# SC_customized2.net
KiCad netlist of a schematic drawn in EAGLE
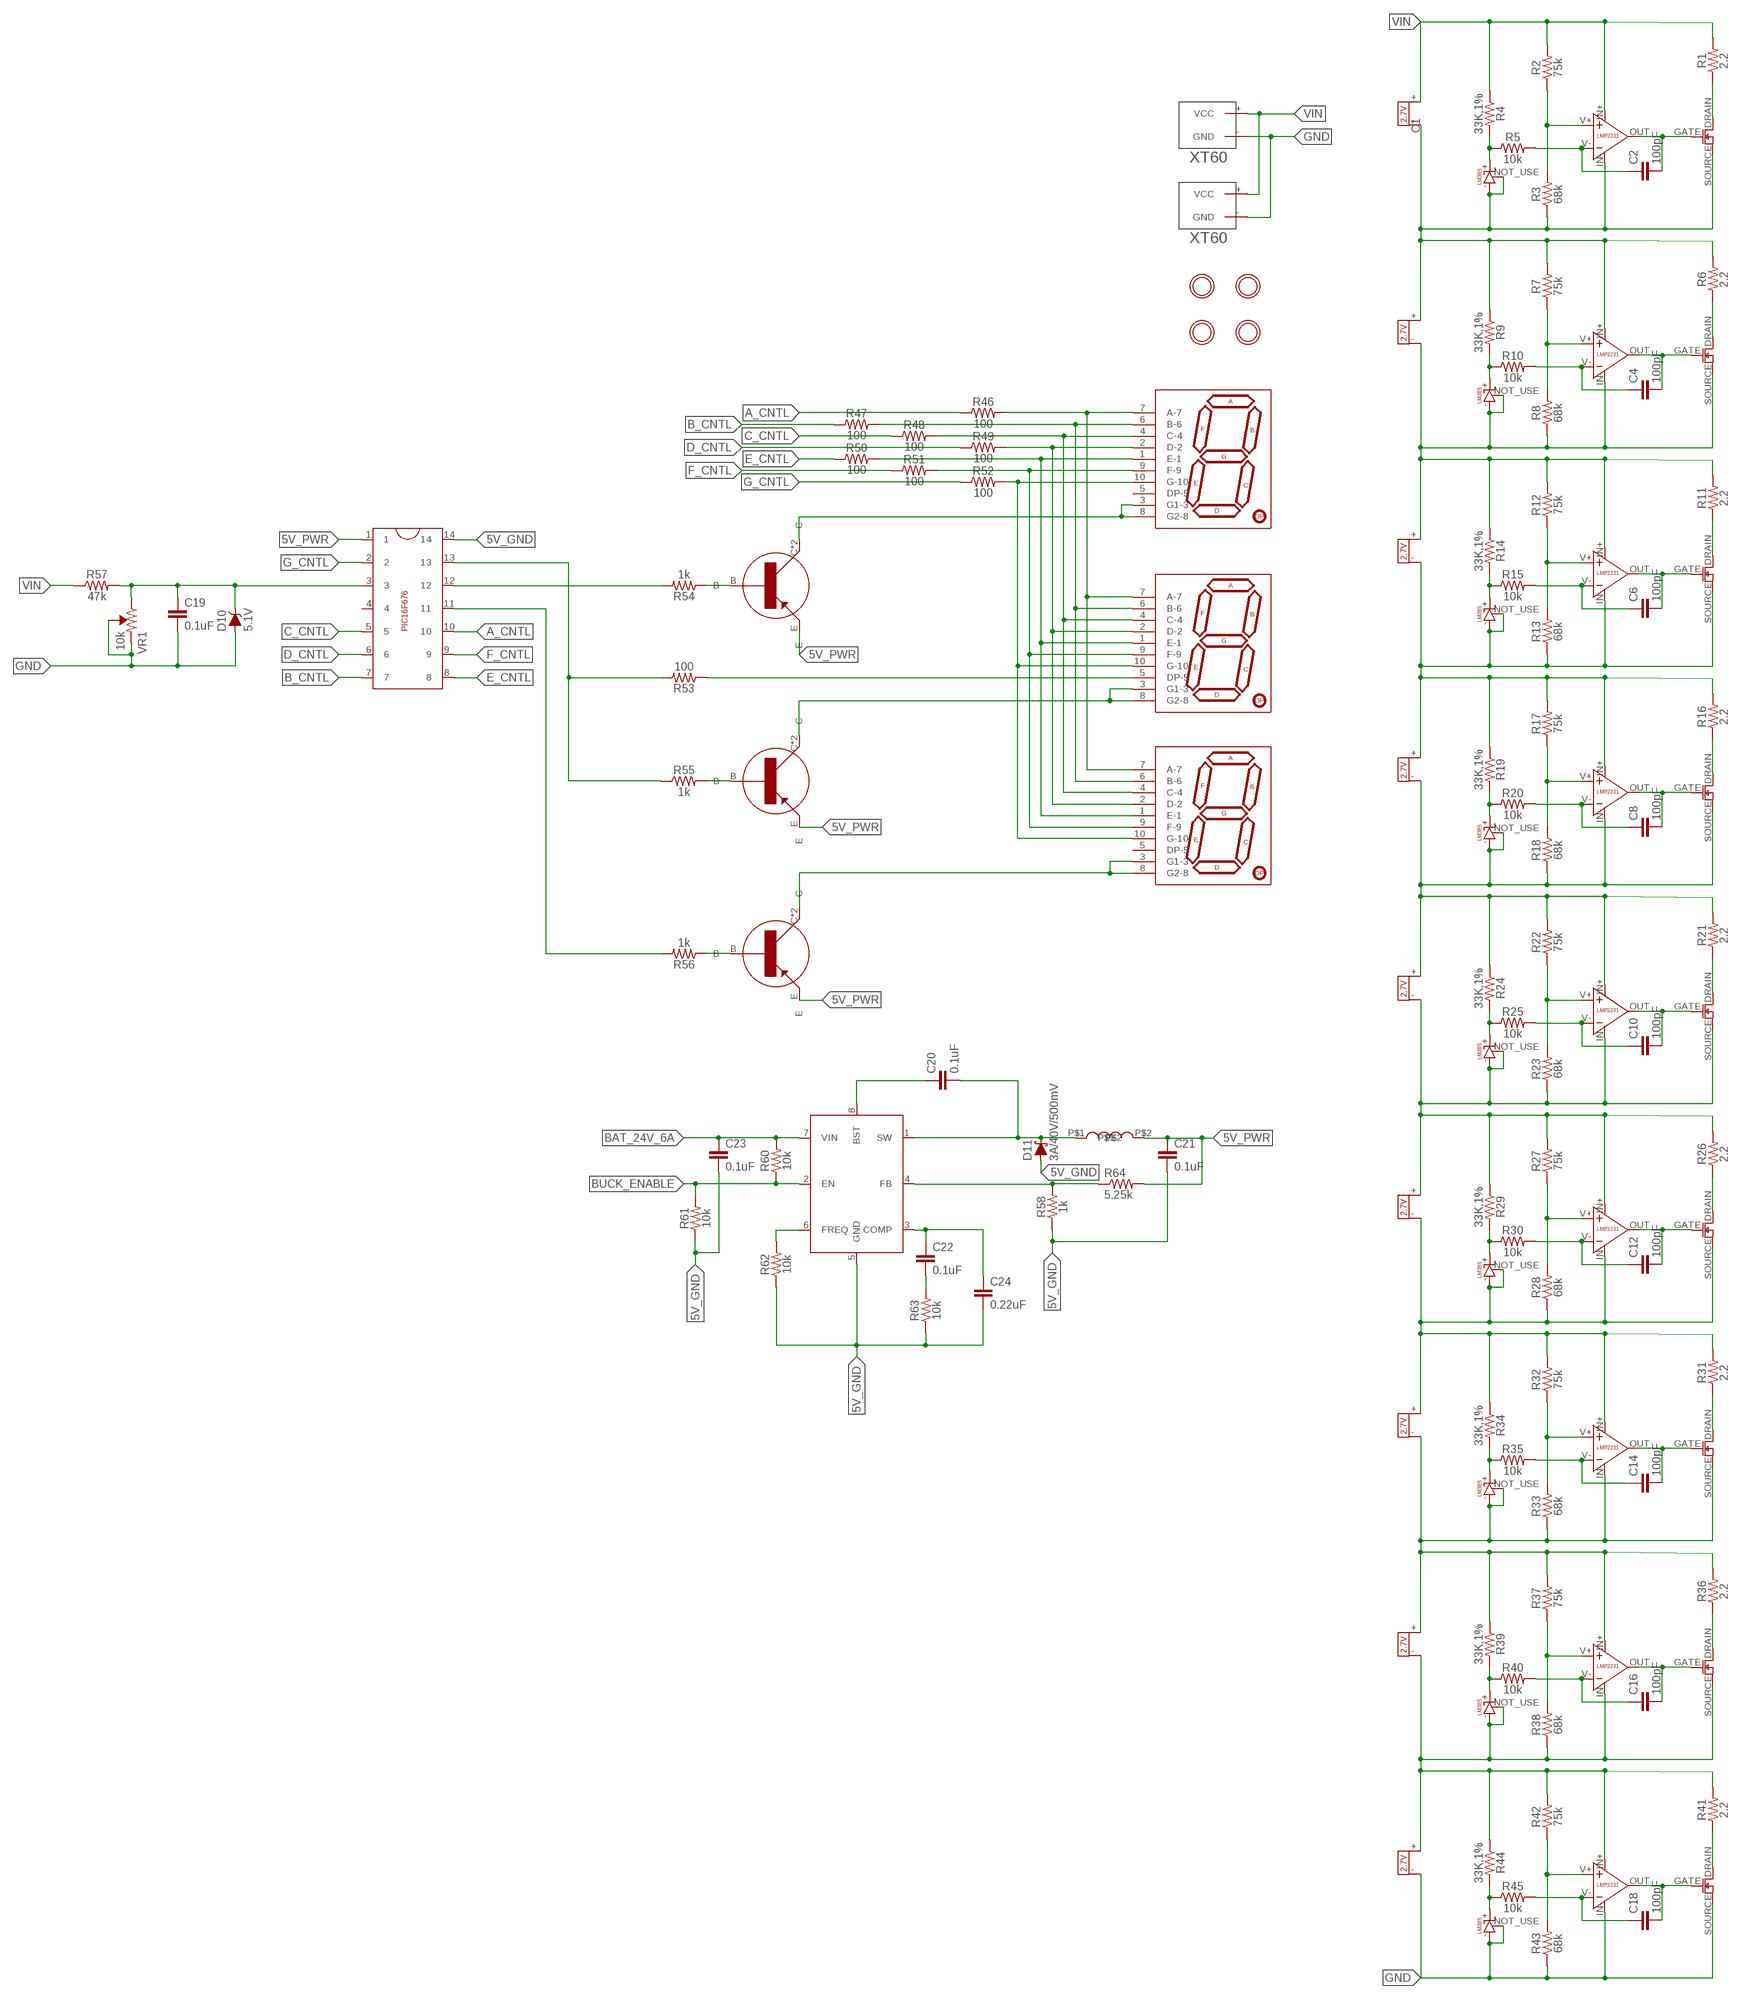
[diagram p0: schematic, sheet 1]

(export (version "E")
  (design (tool "Eeschema 10.0.6"))
  (components
    (comp (ref "3.3V_BUCK")
      (value "SOIC8E")
      (footprint "eagle-import:SOIC127P600X170-9N")
      (libsource (lib "eagle-import") (part "SOIC8E"))
    )
    (comp (ref "C1")
      (value "2.7V 60F")
      (footprint "eagle-import:2.7V_60F")
      (libsource (lib "eagle-import") (part "2.7V_60F"))
    )
    (comp (ref "C2")
      (value "100pF")
      (footprint "eagle-import:0603")
      (libsource (lib "eagle-import") (part "100PF-0603-50V-5%"))
    )
    (comp (ref "C3")
      (value "2.7V 60F")
      (footprint "eagle-import:2.7V_60F")
      (libsource (lib "eagle-import") (part "2.7V_60F"))
    )
    (comp (ref "C4")
      (value "100pF")
      (footprint "eagle-import:0603")
      (libsource (lib "eagle-import") (part "100PF-0603-50V-5%"))
    )
    (comp (ref "C5")
      (value "2.7V 60F")
      (footprint "eagle-import:2.7V_60F")
      (libsource (lib "eagle-import") (part "2.7V_60F"))
    )
    (comp (ref "C6")
      (value "100pF")
      (footprint "eagle-import:0603")
      (libsource (lib "eagle-import") (part "100PF-0603-50V-5%"))
    )
    (comp (ref "C7")
      (value "2.7V 60F")
      (footprint "eagle-import:2.7V_60F")
      (libsource (lib "eagle-import") (part "2.7V_60F"))
    )
    (comp (ref "C8")
      (value "100pF")
      (footprint "eagle-import:0603")
      (libsource (lib "eagle-import") (part "100PF-0603-50V-5%"))
    )
    (comp (ref "C9")
      (value "2.7V 60F")
      (footprint "eagle-import:2.7V_60F")
      (libsource (lib "eagle-import") (part "2.7V_60F"))
    )
    (comp (ref "C10")
      (value "100pF")
      (footprint "eagle-import:0603")
      (libsource (lib "eagle-import") (part "100PF-0603-50V-5%"))
    )
    (comp (ref "C11")
      (value "2.7V 60F")
      (footprint "eagle-import:2.7V_60F")
      (libsource (lib "eagle-import") (part "2.7V_60F"))
    )
    (comp (ref "C12")
      (value "100pF")
      (footprint "eagle-import:0603")
      (libsource (lib "eagle-import") (part "100PF-0603-50V-5%"))
    )
    (comp (ref "C13")
      (value "2.7V 60F")
      (footprint "eagle-import:2.7V_60F")
      (libsource (lib "eagle-import") (part "2.7V_60F"))
    )
    (comp (ref "C14")
      (value "100pF")
      (footprint "eagle-import:0603")
      (libsource (lib "eagle-import") (part "100PF-0603-50V-5%"))
    )
    (comp (ref "C15")
      (value "2.7V 60F")
      (footprint "eagle-import:2.7V_60F")
      (libsource (lib "eagle-import") (part "2.7V_60F"))
    )
    (comp (ref "C16")
      (value "100pF")
      (footprint "eagle-import:0603")
      (libsource (lib "eagle-import") (part "100PF-0603-50V-5%"))
    )
    (comp (ref "C17")
      (value "2.7V 60F")
      (footprint "eagle-import:2.7V_60F")
      (libsource (lib "eagle-import") (part "2.7V_60F"))
    )
    (comp (ref "C18")
      (value "100pF")
      (footprint "eagle-import:0603")
      (libsource (lib "eagle-import") (part "100PF-0603-50V-5%"))
    )
    (comp (ref "C19")
      (value "0.1uF")
      (footprint "eagle-import:0603")
      (libsource (lib "eagle-import") (part "SparkFun-Capacitors_510_0.1UF-0603-25V-5%"))
    )
    (comp (ref "C20")
      (value "0.1uF")
      (footprint "eagle-import:0603")
      (libsource (lib "eagle-import") (part "0.1UF-0603-25V-(+80/-20%)"))
    )
    (comp (ref "C21")
      (value "0.1uF")
      (footprint "eagle-import:0603")
      (libsource (lib "eagle-import") (part "0.1UF-0603-25V-(+80/-20%)"))
    )
    (comp (ref "C22")
      (value "0.1uF")
      (footprint "eagle-import:0603")
      (libsource (lib "eagle-import") (part "0.1UF-0603-25V-(+80/-20%)"))
    )
    (comp (ref "C23")
      (value "0.1uF")
      (footprint "eagle-import:0603")
      (libsource (lib "eagle-import") (part "0.1UF-0603-25V-(+80/-20%)"))
    )
    (comp (ref "C24")
      (value "0.22uF")
      (footprint "eagle-import:0603")
      (libsource (lib "eagle-import") (part "0.22UF-0603-50V-(-20/+80%)"))
    )
    (comp (ref "D1")
      (value "LM385")
      (footprint "eagle-import:LM385_SOT23")
      (libsource (lib "eagle-import") (part "LM385"))
    )
    (comp (ref "D2")
      (value "LM385")
      (footprint "eagle-import:LM385_SOT23")
      (libsource (lib "eagle-import") (part "LM385"))
    )
    (comp (ref "D3")
      (value "LM385")
      (footprint "eagle-import:LM385_SOT23")
      (libsource (lib "eagle-import") (part "LM385"))
    )
    (comp (ref "D4")
      (value "LM385")
      (footprint "eagle-import:LM385_SOT23")
      (libsource (lib "eagle-import") (part "LM385"))
    )
    (comp (ref "D5")
      (value "LM385")
      (footprint "eagle-import:LM385_SOT23")
      (libsource (lib "eagle-import") (part "LM385"))
    )
    (comp (ref "D6")
      (value "LM385")
      (footprint "eagle-import:LM385_SOT23")
      (libsource (lib "eagle-import") (part "LM385"))
    )
    (comp (ref "D7")
      (value "LM385")
      (footprint "eagle-import:LM385_SOT23")
      (libsource (lib "eagle-import") (part "LM385"))
    )
    (comp (ref "D8")
      (value "LM385")
      (footprint "eagle-import:LM385_SOT23")
      (libsource (lib "eagle-import") (part "LM385"))
    )
    (comp (ref "D9")
      (value "LM385")
      (footprint "eagle-import:LM385_SOT23")
      (libsource (lib "eagle-import") (part "LM385"))
    )
    (comp (ref "D10")
      (value "5.1V")
      (footprint "eagle-import:SOD-323")
      (libsource (lib "eagle-import") (part "DIODE-ZENER-MMSZ5232BS"))
    )
    (comp (ref "D11")
      (value "3A/40V/500mV")
      (footprint "eagle-import:SMA-DIODE")
      (libsource (lib "eagle-import") (part "DIODE-SCHOTTKY-B340A"))
    )
    (comp (ref "LMP1")
      (value "LMP2231")
      (footprint "eagle-import:LMP2231_SOT23_5")
      (libsource (lib "eagle-import") (part "LMP2231"))
    )
    (comp (ref "LMP2")
      (value "LMP2231")
      (footprint "eagle-import:LMP2231_SOT23_5")
      (libsource (lib "eagle-import") (part "LMP2231"))
    )
    (comp (ref "LMP3")
      (value "LMP2231")
      (footprint "eagle-import:LMP2231_SOT23_5")
      (libsource (lib "eagle-import") (part "LMP2231"))
    )
    (comp (ref "LMP4")
      (value "LMP2231")
      (footprint "eagle-import:LMP2231_SOT23_5")
      (libsource (lib "eagle-import") (part "LMP2231"))
    )
    (comp (ref "LMP5")
      (value "LMP2231")
      (footprint "eagle-import:LMP2231_SOT23_5")
      (libsource (lib "eagle-import") (part "LMP2231"))
    )
    (comp (ref "LMP6")
      (value "LMP2231")
      (footprint "eagle-import:LMP2231_SOT23_5")
      (libsource (lib "eagle-import") (part "LMP2231"))
    )
    (comp (ref "LMP7")
      (value "LMP2231")
      (footprint "eagle-import:LMP2231_SOT23_5")
      (libsource (lib "eagle-import") (part "LMP2231"))
    )
    (comp (ref "LMP8")
      (value "LMP2231")
      (footprint "eagle-import:LMP2231_SOT23_5")
      (libsource (lib "eagle-import") (part "LMP2231"))
    )
    (comp (ref "LMP9")
      (value "LMP2231")
      (footprint "eagle-import:LMP2231_SOT23_5")
      (libsource (lib "eagle-import") (part "LMP2231"))
    )
    (comp (ref "MOS1")
      (value "IRLML2502TRPBF_MOS")
      (footprint "eagle-import:IRLML2502TRPBF_SOT23")
      (libsource (lib "eagle-import") (part "IRLML2502TRPBF_MOS"))
    )
    (comp (ref "MOS2")
      (value "IRLML2502TRPBF_MOS")
      (footprint "eagle-import:IRLML2502TRPBF_SOT23")
      (libsource (lib "eagle-import") (part "IRLML2502TRPBF_MOS"))
    )
    (comp (ref "MOS3")
      (value "IRLML2502TRPBF_MOS")
      (footprint "eagle-import:IRLML2502TRPBF_SOT23")
      (libsource (lib "eagle-import") (part "IRLML2502TRPBF_MOS"))
    )
    (comp (ref "MOS4")
      (value "IRLML2502TRPBF_MOS")
      (footprint "eagle-import:IRLML2502TRPBF_SOT23")
      (libsource (lib "eagle-import") (part "IRLML2502TRPBF_MOS"))
    )
    (comp (ref "MOS5")
      (value "IRLML2502TRPBF_MOS")
      (footprint "eagle-import:IRLML2502TRPBF_SOT23")
      (libsource (lib "eagle-import") (part "IRLML2502TRPBF_MOS"))
    )
    (comp (ref "MOS6")
      (value "IRLML2502TRPBF_MOS")
      (footprint "eagle-import:IRLML2502TRPBF_SOT23")
      (libsource (lib "eagle-import") (part "IRLML2502TRPBF_MOS"))
    )
    (comp (ref "MOS7")
      (value "IRLML2502TRPBF_MOS")
      (footprint "eagle-import:IRLML2502TRPBF_SOT23")
      (libsource (lib "eagle-import") (part "IRLML2502TRPBF_MOS"))
    )
    (comp (ref "MOS8")
      (value "IRLML2502TRPBF_MOS")
      (footprint "eagle-import:IRLML2502TRPBF_SOT23")
      (libsource (lib "eagle-import") (part "IRLML2502TRPBF_MOS"))
    )
    (comp (ref "MOS9")
      (value "IRLML2502TRPBF_MOS")
      (footprint "eagle-import:IRLML2502TRPBF_SOT23")
      (libsource (lib "eagle-import") (part "IRLML2502TRPBF_MOS"))
    )
    (comp (ref "PWR_IN")
      (value "XT60")
      (footprint "eagle-import:XT60")
      (libsource (lib "eagle-import") (part "XT60"))
    )
    (comp (ref "PWR_OUT")
      (value "XT60")
      (footprint "eagle-import:XT60")
      (libsource (lib "eagle-import") (part "XT60"))
    )
    (comp (ref "R1")
      (value "2.2")
      (footprint "eagle-import:2512")
      (libsource (lib "eagle-import") (part "0.05OHM-2512-3W-1%"))
    )
    (comp (ref "R2")
      (value "75k")
      (footprint "eagle-import:0603@1")
      (libsource (lib "eagle-import") (part "75KOHM-0603-1/10W-1%"))
    )
    (comp (ref "R3")
      (value "68k")
      (footprint "eagle-import:0603@1")
      (libsource (lib "eagle-import") (part "75KOHM-0603-1/10W-1%"))
    )
    (comp (ref "R4")
      (value "33K,1%")
      (footprint "eagle-import:0603@1")
      (libsource (lib "eagle-import") (part "1MOHM-0603-1/4W-5%"))
    )
    (comp (ref "R5")
      (value "10k")
      (footprint "eagle-import:0603")
      (libsource (lib "eagle-import") (part "10KOHM-0603-1/10W-1%"))
    )
    (comp (ref "R6")
      (value "2.2")
      (footprint "eagle-import:2512")
      (libsource (lib "eagle-import") (part "0.05OHM-2512-3W-1%"))
    )
    (comp (ref "R7")
      (value "75k")
      (footprint "eagle-import:0603@1")
      (libsource (lib "eagle-import") (part "75KOHM-0603-1/10W-1%"))
    )
    (comp (ref "R8")
      (value "68k")
      (footprint "eagle-import:0603@1")
      (libsource (lib "eagle-import") (part "75KOHM-0603-1/10W-1%"))
    )
    (comp (ref "R9")
      (value "33K,1%")
      (footprint "eagle-import:0603@1")
      (libsource (lib "eagle-import") (part "1MOHM-0603-1/4W-5%"))
    )
    (comp (ref "R10")
      (value "10k")
      (footprint "eagle-import:0603")
      (libsource (lib "eagle-import") (part "10KOHM-0603-1/10W-1%"))
    )
    (comp (ref "R11")
      (value "2.2")
      (footprint "eagle-import:2512")
      (libsource (lib "eagle-import") (part "0.05OHM-2512-3W-1%"))
    )
    (comp (ref "R12")
      (value "75k")
      (footprint "eagle-import:0603@1")
      (libsource (lib "eagle-import") (part "75KOHM-0603-1/10W-1%"))
    )
    (comp (ref "R13")
      (value "68k")
      (footprint "eagle-import:0603@1")
      (libsource (lib "eagle-import") (part "75KOHM-0603-1/10W-1%"))
    )
    (comp (ref "R14")
      (value "33K,1%")
      (footprint "eagle-import:0603@1")
      (libsource (lib "eagle-import") (part "1MOHM-0603-1/4W-5%"))
    )
    (comp (ref "R15")
      (value "10k")
      (footprint "eagle-import:0603")
      (libsource (lib "eagle-import") (part "10KOHM-0603-1/10W-1%"))
    )
    (comp (ref "R16")
      (value "2.2")
      (footprint "eagle-import:2512")
      (libsource (lib "eagle-import") (part "0.05OHM-2512-3W-1%"))
    )
    (comp (ref "R17")
      (value "75k")
      (footprint "eagle-import:0603@1")
      (libsource (lib "eagle-import") (part "75KOHM-0603-1/10W-1%"))
    )
    (comp (ref "R18")
      (value "68k")
      (footprint "eagle-import:0603@1")
      (libsource (lib "eagle-import") (part "75KOHM-0603-1/10W-1%"))
    )
    (comp (ref "R19")
      (value "33K,1%")
      (footprint "eagle-import:0603@1")
      (libsource (lib "eagle-import") (part "1MOHM-0603-1/4W-5%"))
    )
    (comp (ref "R20")
      (value "10k")
      (footprint "eagle-import:0603")
      (libsource (lib "eagle-import") (part "10KOHM-0603-1/10W-1%"))
    )
    (comp (ref "R21")
      (value "2.2")
      (footprint "eagle-import:2512")
      (libsource (lib "eagle-import") (part "0.05OHM-2512-3W-1%"))
    )
    (comp (ref "R22")
      (value "75k")
      (footprint "eagle-import:0603@1")
      (libsource (lib "eagle-import") (part "75KOHM-0603-1/10W-1%"))
    )
    (comp (ref "R23")
      (value "68k")
      (footprint "eagle-import:0603@1")
      (libsource (lib "eagle-import") (part "75KOHM-0603-1/10W-1%"))
    )
    (comp (ref "R24")
      (value "33K,1%")
      (footprint "eagle-import:0603@1")
      (libsource (lib "eagle-import") (part "1MOHM-0603-1/4W-5%"))
    )
    (comp (ref "R25")
      (value "10k")
      (footprint "eagle-import:0603")
      (libsource (lib "eagle-import") (part "10KOHM-0603-1/10W-1%"))
    )
    (comp (ref "R26")
      (value "2.2")
      (footprint "eagle-import:2512")
      (libsource (lib "eagle-import") (part "0.05OHM-2512-3W-1%"))
    )
    (comp (ref "R27")
      (value "75k")
      (footprint "eagle-import:0603@1")
      (libsource (lib "eagle-import") (part "75KOHM-0603-1/10W-1%"))
    )
    (comp (ref "R28")
      (value "68k")
      (footprint "eagle-import:0603@1")
      (libsource (lib "eagle-import") (part "75KOHM-0603-1/10W-1%"))
    )
    (comp (ref "R29")
      (value "33K,1%")
      (footprint "eagle-import:0603@1")
      (libsource (lib "eagle-import") (part "1MOHM-0603-1/4W-5%"))
    )
    (comp (ref "R30")
      (value "10k")
      (footprint "eagle-import:0603")
      (libsource (lib "eagle-import") (part "10KOHM-0603-1/10W-1%"))
    )
    (comp (ref "R31")
      (value "2.2")
      (footprint "eagle-import:2512")
      (libsource (lib "eagle-import") (part "0.05OHM-2512-3W-1%"))
    )
    (comp (ref "R32")
      (value "75k")
      (footprint "eagle-import:0603@1")
      (libsource (lib "eagle-import") (part "75KOHM-0603-1/10W-1%"))
    )
    (comp (ref "R33")
      (value "68k")
      (footprint "eagle-import:0603@1")
      (libsource (lib "eagle-import") (part "75KOHM-0603-1/10W-1%"))
    )
    (comp (ref "R34")
      (value "33K,1%")
      (footprint "eagle-import:0603@1")
      (libsource (lib "eagle-import") (part "1MOHM-0603-1/4W-5%"))
    )
    (comp (ref "R35")
      (value "10k")
      (footprint "eagle-import:0603")
      (libsource (lib "eagle-import") (part "10KOHM-0603-1/10W-1%"))
    )
    (comp (ref "R36")
      (value "2.2")
      (footprint "eagle-import:2512")
      (libsource (lib "eagle-import") (part "0.05OHM-2512-3W-1%"))
    )
    (comp (ref "R37")
      (value "75k")
      (footprint "eagle-import:0603@1")
      (libsource (lib "eagle-import") (part "75KOHM-0603-1/10W-1%"))
    )
    (comp (ref "R38")
      (value "68k")
      (footprint "eagle-import:0603@1")
      (libsource (lib "eagle-import") (part "75KOHM-0603-1/10W-1%"))
    )
    (comp (ref "R39")
      (value "33K,1%")
      (footprint "eagle-import:0603@1")
      (libsource (lib "eagle-import") (part "1MOHM-0603-1/4W-5%"))
    )
    (comp (ref "R40")
      (value "10k")
      (footprint "eagle-import:0603")
      (libsource (lib "eagle-import") (part "10KOHM-0603-1/10W-1%"))
    )
    (comp (ref "R41")
      (value "2.2")
      (footprint "eagle-import:2512")
      (libsource (lib "eagle-import") (part "0.05OHM-2512-3W-1%"))
    )
    (comp (ref "R42")
      (value "75k")
      (footprint "eagle-import:0603@1")
      (libsource (lib "eagle-import") (part "75KOHM-0603-1/10W-1%"))
    )
    (comp (ref "R43")
      (value "68k")
      (footprint "eagle-import:0603@1")
      (libsource (lib "eagle-import") (part "75KOHM-0603-1/10W-1%"))
    )
    (comp (ref "R44")
      (value "33K,1%")
      (footprint "eagle-import:0603@1")
      (libsource (lib "eagle-import") (part "1MOHM-0603-1/4W-5%"))
    )
    (comp (ref "R45")
      (value "10k")
      (footprint "eagle-import:0603")
      (libsource (lib "eagle-import") (part "10KOHM-0603-1/10W-1%"))
    )
    (comp (ref "R46")
      (value "100")
      (footprint "eagle-import:0603")
      (libsource (lib "eagle-import") (part "100OHM-0603-1/4W-5%"))
    )
    (comp (ref "R47")
      (value "100")
      (footprint "eagle-import:0603")
      (libsource (lib "eagle-import") (part "100OHM-0603-1/4W-5%"))
    )
    (comp (ref "R48")
      (value "100")
      (footprint "eagle-import:0603")
      (libsource (lib "eagle-import") (part "100OHM-0603-1/4W-5%"))
    )
    (comp (ref "R49")
      (value "100")
      (footprint "eagle-import:0603")
      (libsource (lib "eagle-import") (part "100OHM-0603-1/4W-5%"))
    )
    (comp (ref "R50")
      (value "100")
      (footprint "eagle-import:0603")
      (libsource (lib "eagle-import") (part "100OHM-0603-1/4W-5%"))
    )
    (comp (ref "R51")
      (value "100")
      (footprint "eagle-import:0603")
      (libsource (lib "eagle-import") (part "100OHM-0603-1/4W-5%"))
    )
    (comp (ref "R52")
      (value "100")
      (footprint "eagle-import:0603")
      (libsource (lib "eagle-import") (part "100OHM-0603-1/4W-5%"))
    )
    (comp (ref "R53")
      (value "100")
      (footprint "eagle-import:0603")
      (libsource (lib "eagle-import") (part "100OHM-0603-1/4W-5%"))
    )
    (comp (ref "R54")
      (value "1k")
      (footprint "eagle-import:0603")
      (libsource (lib "eagle-import") (part "SparkFun-Resistors_532_1KOHM-0603-1/10W-1%"))
    )
    (comp (ref "R55")
      (value "1k")
      (footprint "eagle-import:0603")
      (libsource (lib "eagle-import") (part "SparkFun-Resistors_532_1KOHM-0603-1/10W-1%"))
    )
    (comp (ref "R56")
      (value "1k")
      (footprint "eagle-import:0603")
      (libsource (lib "eagle-import") (part "SparkFun-Resistors_532_1KOHM-0603-1/10W-1%"))
    )
    (comp (ref "R57")
      (value "47k")
      (footprint "eagle-import:0603")
      (libsource (lib "eagle-import") (part "47KOHM-0603-1/10W-1%"))
    )
    (comp (ref "R58")
      (value "1k")
      (footprint "eagle-import:0603")
      (libsource (lib "eagle-import") (part "1KOHM-0603-1/10W-1%"))
    )
    (comp (ref "R60")
      (value "10k")
      (footprint "eagle-import:0603")
      (libsource (lib "eagle-import") (part "10KOHM-0603-1/10W-1%"))
    )
    (comp (ref "R61")
      (value "10k")
      (footprint "eagle-import:0603")
      (libsource (lib "eagle-import") (part "10KOHM-0603-1/10W-1%"))
    )
    (comp (ref "R62")
      (value "10k")
      (footprint "eagle-import:0603")
      (libsource (lib "eagle-import") (part "10KOHM-0603-1/10W-1%"))
    )
    (comp (ref "R63")
      (value "10k")
      (footprint "eagle-import:0603")
      (libsource (lib "eagle-import") (part "10KOHM-0603-1/10W-1%"))
    )
    (comp (ref "R64")
      (value "5.25k")
      (footprint "eagle-import:RES_0805")
      (fields
        (field (name "DIGIKEY_PART_NUMBER") "541-0.0ATR-ND")
        (field (name "MANUFACTURER") "Vishay Dale")
        (field (name "MPN") "CRCW08050000Z0EA")
        (field (name "CREATED_BY") "PCBLayout.com")
      )
      (libsource (lib "eagle-import") (part "CRCW08050000Z0EA"))
    )
    (comp (ref "U$1")
      (value "MOUNTINGHOLE2.5")
      (footprint "eagle-import:MOUNTINGHOLE_2.5_PLATED")
      (libsource (lib "eagle-import") (part "MOUNTINGHOLE2.5"))
    )
    (comp (ref "U$2")
      (value "MOUNTINGHOLE2.5")
      (footprint "eagle-import:MOUNTINGHOLE_2.5_PLATED")
      (libsource (lib "eagle-import") (part "MOUNTINGHOLE2.5"))
    )
    (comp (ref "U$3")
      (value "PZT3906")
      (footprint "eagle-import:SOT_223")
      (libsource (lib "eagle-import") (part "PZT3906"))
    )
    (comp (ref "U$4")
      (value "MOUNTINGHOLE2.5")
      (footprint "eagle-import:MOUNTINGHOLE_2.5_PLATED")
      (libsource (lib "eagle-import") (part "MOUNTINGHOLE2.5"))
    )
    (comp (ref "U$5")
      (value "PZT3906")
      (footprint "eagle-import:SOT_223")
      (libsource (lib "eagle-import") (part "PZT3906"))
    )
    (comp (ref "U$6")
      (value "PZT3906")
      (footprint "eagle-import:SOT_223")
      (libsource (lib "eagle-import") (part "PZT3906"))
    )
    (comp (ref "U$7")
      (value "DSM7T")
      (footprint "eagle-import:7-SEGMENT_SMD")
      (libsource (lib "eagle-import") (part "DSM7T"))
    )
    (comp (ref "U$8")
      (value "DSM7T")
      (footprint "eagle-import:7-SEGMENT_SMD")
      (libsource (lib "eagle-import") (part "DSM7T"))
    )
    (comp (ref "U$9")
      (value "DSM7T")
      (footprint "eagle-import:7-SEGMENT_SMD")
      (libsource (lib "eagle-import") (part "DSM7T"))
    )
    (comp (ref "U$10")
      (value "PIC16F676")
      (footprint "eagle-import:PIC16F676")
      (libsource (lib "eagle-import") (part "PIC16F676"))
    )
    (comp (ref "U$11")
      (value "4.7UH_INDUCTOR")
      (footprint "eagle-import:4.7UH_INDUCTOR")
      (libsource (lib "eagle-import") (part "4.7UH_INDUCTOR"))
    )
    (comp (ref "U$49")
      (value "MOUNTINGHOLE2.5")
      (footprint "eagle-import:MOUNTINGHOLE_2.5_PLATED")
      (libsource (lib "eagle-import") (part "MOUNTINGHOLE2.5"))
    )
    (comp (ref "VR1")
      (value "10k")
      (footprint "eagle-import:TRIMPOT-SMD-TC33X")
      (libsource (lib "eagle-import") (part "TRIMPOT-SMD-3MM-OPEN-1/10W-25%"))
    )
  )
  (nets
    (net (code "1") (name "5V_GND") (class "Default")
      (node (ref "3.3V_BUCK") (pin "5") (pinfunction "GND_5") (pintype "bidirectional"))
      (node (ref "C21") (pin "2") (pinfunction "2_2") (pintype "passive"))
      (node (ref "C23") (pin "2") (pinfunction "2_2") (pintype "passive"))
      (node (ref "C24") (pin "2") (pinfunction "2_2") (pintype "passive"))
      (node (ref "D11") (pin "A") (pinfunction "A_A") (pintype "passive"))
      (node (ref "R58") (pin "1") (pinfunction "1_1") (pintype "passive"))
      (node (ref "R61") (pin "1") (pinfunction "1_1") (pintype "passive"))
      (node (ref "R62") (pin "1") (pinfunction "1_1") (pintype "passive"))
      (node (ref "R63") (pin "1") (pinfunction "1_1") (pintype "passive"))
      (node (ref "U$10") (pin "14") (pinfunction "14_14") (pintype "bidirectional"))
    )
    (net (code "2") (name "5V_PWR") (class "Default")
      (node (ref "C21") (pin "1") (pinfunction "1_1") (pintype "passive"))
      (node (ref "R64") (pin "2") (pinfunction "2_2") (pintype "passive"))
      (node (ref "U$10") (pin "1") (pinfunction "1_1") (pintype "bidirectional"))
      (node (ref "U$11") (pin "P$2") (pinfunction "P$2_P$2") (pintype "bidirectional"))
      (node (ref "U$3") (pin "E") (pinfunction "E_E") (pintype "bidirectional"))
      (node (ref "U$5") (pin "E") (pinfunction "E_E") (pintype "bidirectional"))
      (node (ref "U$6") (pin "E") (pinfunction "E_E") (pintype "bidirectional"))
    )
    (net (code "3") (name "A_CNTL") (class "Default")
      (node (ref "R46") (pin "1") (pinfunction "1_1") (pintype "passive"))
      (node (ref "U$10") (pin "10") (pinfunction "10_10") (pintype "bidirectional"))
    )
    (net (code "4") (name "BAT_24V_6A") (class "Default")
      (node (ref "3.3V_BUCK") (pin "7") (pinfunction "VIN_7") (pintype "bidirectional"))
      (node (ref "C23") (pin "1") (pinfunction "1_1") (pintype "passive"))
      (node (ref "R60") (pin "2") (pinfunction "2_2") (pintype "passive"))
    )
    (net (code "5") (name "BUCK_ENABLE") (class "Default")
      (node (ref "3.3V_BUCK") (pin "2") (pinfunction "EN_2") (pintype "bidirectional"))
      (node (ref "R60") (pin "1") (pinfunction "1_1") (pintype "passive"))
      (node (ref "R61") (pin "2") (pinfunction "2_2") (pintype "passive"))
    )
    (net (code "6") (name "B_CNTL") (class "Default")
      (node (ref "R47") (pin "1") (pinfunction "1_1") (pintype "passive"))
      (node (ref "U$10") (pin "7") (pinfunction "7_7") (pintype "bidirectional"))
    )
    (net (code "7") (name "C_CNTL") (class "Default")
      (node (ref "R48") (pin "1") (pinfunction "1_1") (pintype "passive"))
      (node (ref "U$10") (pin "5") (pinfunction "5_5") (pintype "bidirectional"))
    )
    (net (code "8") (name "D_CNTL") (class "Default")
      (node (ref "R49") (pin "1") (pinfunction "1_1") (pintype "passive"))
      (node (ref "U$10") (pin "6") (pinfunction "6_6") (pintype "bidirectional"))
    )
    (net (code "9") (name "E_CNTL") (class "Default")
      (node (ref "R50") (pin "1") (pinfunction "1_1") (pintype "passive"))
      (node (ref "U$10") (pin "8") (pinfunction "8_8") (pintype "bidirectional"))
    )
    (net (code "10") (name "F_CNTL") (class "Default")
      (node (ref "R51") (pin "1") (pinfunction "1_1") (pintype "passive"))
      (node (ref "U$10") (pin "9") (pinfunction "9_9") (pintype "bidirectional"))
    )
    (net (code "11") (name "GND") (class "Default")
      (node (ref "C17") (pin "-") (pinfunction "-_-") (pintype "bidirectional"))
      (node (ref "C19") (pin "2") (pinfunction "2_2") (pintype "passive"))
      (node (ref "D10") (pin "A") (pinfunction "A_A") (pintype "passive"))
      (node (ref "D9") (pin "-") (pinfunction "-_-") (pintype "bidirectional"))
      (node (ref "D9") (pin "NOT_USE") (pinfunction "NOT_USE_NOT_USE") (pintype "bidirectional"))
      (node (ref "LMP9") (pin "IN-") (pinfunction "IN-_IN-") (pintype "bidirectional"))
      (node (ref "MOS9") (pin "SOURCE") (pinfunction "SOURCE_SOURCE") (pintype "bidirectional"))
      (node (ref "PWR_IN") (pin "-") (pinfunction "GND_-") (pintype "bidirectional"))
      (node (ref "PWR_OUT") (pin "-") (pinfunction "GND_-") (pintype "bidirectional"))
      (node (ref "R43") (pin "1") (pinfunction "1_1") (pintype "passive"))
      (node (ref "VR1") (pin "2") (pinfunction "WIPER_2") (pintype "passive"))
      (node (ref "VR1") (pin "3") (pinfunction "CCW_3") (pintype "passive"))
    )
    (net (code "12") (name "G_CNTL") (class "Default")
      (node (ref "R52") (pin "1") (pinfunction "1_1") (pintype "passive"))
      (node (ref "U$10") (pin "2") (pinfunction "2_2") (pintype "bidirectional"))
    )
    (net (code "13") (name "Net-(3.3V_BUCK-BST)") (class "Default")
      (node (ref "3.3V_BUCK") (pin "8") (pinfunction "BST_8") (pintype "bidirectional"))
      (node (ref "C20") (pin "1") (pinfunction "1_1") (pintype "passive"))
    )
    (net (code "14") (name "Net-(3.3V_BUCK-COMP)") (class "Default")
      (node (ref "3.3V_BUCK") (pin "3") (pinfunction "COMP_3") (pintype "bidirectional"))
      (node (ref "C22") (pin "1") (pinfunction "1_1") (pintype "passive"))
      (node (ref "C24") (pin "1") (pinfunction "1_1") (pintype "passive"))
    )
    (net (code "15") (name "Net-(3.3V_BUCK-FB)") (class "Default")
      (node (ref "3.3V_BUCK") (pin "4") (pinfunction "FB_4") (pintype "bidirectional"))
      (node (ref "R58") (pin "2") (pinfunction "2_2") (pintype "passive"))
      (node (ref "R64") (pin "1") (pinfunction "1_1") (pintype "passive"))
    )
    (net (code "16") (name "Net-(3.3V_BUCK-FREQ)") (class "Default")
      (node (ref "3.3V_BUCK") (pin "6") (pinfunction "FREQ_6") (pintype "bidirectional"))
      (node (ref "R62") (pin "2") (pinfunction "2_2") (pintype "passive"))
    )
    (net (code "17") (name "Net-(3.3V_BUCK-SW)") (class "Default")
      (node (ref "3.3V_BUCK") (pin "1") (pinfunction "SW_1") (pintype "bidirectional"))
      (node (ref "C20") (pin "2") (pinfunction "2_2") (pintype "passive"))
      (node (ref "D11") (pin "C") (pinfunction "C_C") (pintype "passive"))
      (node (ref "U$11") (pin "P$1") (pinfunction "P$1_P$1") (pintype "bidirectional"))
    )
    (net (code "18") (name "Net-(C2-Pad1)") (class "Default")
      (node (ref "C2") (pin "1") (pinfunction "1_1") (pintype "passive"))
      (node (ref "LMP1") (pin "V-") (pinfunction "V-_V-") (pintype "bidirectional"))
      (node (ref "R5") (pin "2") (pinfunction "2_2") (pintype "passive"))
    )
    (net (code "19") (name "Net-(C2-Pad2)") (class "Default")
      (node (ref "C2") (pin "2") (pinfunction "2_2") (pintype "passive"))
      (node (ref "LMP1") (pin "OUT") (pinfunction "OUT_OUT") (pintype "bidirectional"))
      (node (ref "MOS1") (pin "GATE") (pinfunction "GATE_GATE") (pintype "bidirectional"))
    )
    (net (code "20") (name "Net-(C4-Pad1)") (class "Default")
      (node (ref "C4") (pin "1") (pinfunction "1_1") (pintype "passive"))
      (node (ref "LMP2") (pin "V-") (pinfunction "V-_V-") (pintype "bidirectional"))
      (node (ref "R10") (pin "2") (pinfunction "2_2") (pintype "passive"))
    )
    (net (code "21") (name "Net-(C4-Pad2)") (class "Default")
      (node (ref "C4") (pin "2") (pinfunction "2_2") (pintype "passive"))
      (node (ref "LMP2") (pin "OUT") (pinfunction "OUT_OUT") (pintype "bidirectional"))
      (node (ref "MOS2") (pin "GATE") (pinfunction "GATE_GATE") (pintype "bidirectional"))
    )
    (net (code "22") (name "Net-(C6-Pad1)") (class "Default")
      (node (ref "C6") (pin "1") (pinfunction "1_1") (pintype "passive"))
      (node (ref "LMP3") (pin "V-") (pinfunction "V-_V-") (pintype "bidirectional"))
      (node (ref "R15") (pin "2") (pinfunction "2_2") (pintype "passive"))
    )
    (net (code "23") (name "Net-(C6-Pad2)") (class "Default")
      (node (ref "C6") (pin "2") (pinfunction "2_2") (pintype "passive"))
      (node (ref "LMP3") (pin "OUT") (pinfunction "OUT_OUT") (pintype "bidirectional"))
      (node (ref "MOS3") (pin "GATE") (pinfunction "GATE_GATE") (pintype "bidirectional"))
    )
    (net (code "24") (name "Net-(C8-Pad1)") (class "Default")
      (node (ref "C8") (pin "1") (pinfunction "1_1") (pintype "passive"))
      (node (ref "LMP4") (pin "V-") (pinfunction "V-_V-") (pintype "bidirectional"))
      (node (ref "R20") (pin "2") (pinfunction "2_2") (pintype "passive"))
    )
    (net (code "25") (name "Net-(C8-Pad2)") (class "Default")
      (node (ref "C8") (pin "2") (pinfunction "2_2") (pintype "passive"))
      (node (ref "LMP4") (pin "OUT") (pinfunction "OUT_OUT") (pintype "bidirectional"))
      (node (ref "MOS4") (pin "GATE") (pinfunction "GATE_GATE") (pintype "bidirectional"))
    )
    (net (code "26") (name "Net-(C10-Pad1)") (class "Default")
      (node (ref "C10") (pin "1") (pinfunction "1_1") (pintype "passive"))
      (node (ref "LMP5") (pin "V-") (pinfunction "V-_V-") (pintype "bidirectional"))
      (node (ref "R25") (pin "2") (pinfunction "2_2") (pintype "passive"))
    )
    (net (code "27") (name "Net-(C10-Pad2)") (class "Default")
      (node (ref "C10") (pin "2") (pinfunction "2_2") (pintype "passive"))
      (node (ref "LMP5") (pin "OUT") (pinfunction "OUT_OUT") (pintype "bidirectional"))
      (node (ref "MOS5") (pin "GATE") (pinfunction "GATE_GATE") (pintype "bidirectional"))
    )
    (net (code "28") (name "Net-(C12-Pad1)") (class "Default")
      (node (ref "C12") (pin "1") (pinfunction "1_1") (pintype "passive"))
      (node (ref "LMP6") (pin "V-") (pinfunction "V-_V-") (pintype "bidirectional"))
      (node (ref "R30") (pin "2") (pinfunction "2_2") (pintype "passive"))
    )
    (net (code "29") (name "Net-(C12-Pad2)") (class "Default")
      (node (ref "C12") (pin "2") (pinfunction "2_2") (pintype "passive"))
      (node (ref "LMP6") (pin "OUT") (pinfunction "OUT_OUT") (pintype "bidirectional"))
      (node (ref "MOS6") (pin "GATE") (pinfunction "GATE_GATE") (pintype "bidirectional"))
    )
    (net (code "30") (name "Net-(C14-Pad1)") (class "Default")
      (node (ref "C14") (pin "1") (pinfunction "1_1") (pintype "passive"))
      (node (ref "LMP7") (pin "V-") (pinfunction "V-_V-") (pintype "bidirectional"))
      (node (ref "R35") (pin "2") (pinfunction "2_2") (pintype "passive"))
    )
    (net (code "31") (name "Net-(C14-Pad2)") (class "Default")
      (node (ref "C14") (pin "2") (pinfunction "2_2") (pintype "passive"))
      (node (ref "LMP7") (pin "OUT") (pinfunction "OUT_OUT") (pintype "bidirectional"))
      (node (ref "MOS7") (pin "GATE") (pinfunction "GATE_GATE") (pintype "bidirectional"))
    )
    (net (code "32") (name "Net-(C16-Pad1)") (class "Default")
      (node (ref "C16") (pin "1") (pinfunction "1_1") (pintype "passive"))
      (node (ref "LMP8") (pin "V-") (pinfunction "V-_V-") (pintype "bidirectional"))
      (node (ref "R40") (pin "2") (pinfunction "2_2") (pintype "passive"))
    )
    (net (code "33") (name "Net-(C16-Pad2)") (class "Default")
      (node (ref "C16") (pin "2") (pinfunction "2_2") (pintype "passive"))
      (node (ref "LMP8") (pin "OUT") (pinfunction "OUT_OUT") (pintype "bidirectional"))
      (node (ref "MOS8") (pin "GATE") (pinfunction "GATE_GATE") (pintype "bidirectional"))
    )
    (net (code "34") (name "Net-(C18-Pad1)") (class "Default")
      (node (ref "C18") (pin "1") (pinfunction "1_1") (pintype "passive"))
      (node (ref "LMP9") (pin "V-") (pinfunction "V-_V-") (pintype "bidirectional"))
      (node (ref "R45") (pin "2") (pinfunction "2_2") (pintype "passive"))
    )
    (net (code "35") (name "Net-(C18-Pad2)") (class "Default")
      (node (ref "C18") (pin "2") (pinfunction "2_2") (pintype "passive"))
      (node (ref "LMP9") (pin "OUT") (pinfunction "OUT_OUT") (pintype "bidirectional"))
      (node (ref "MOS9") (pin "GATE") (pinfunction "GATE_GATE") (pintype "bidirectional"))
    )
    (net (code "36") (name "Net-(C22-Pad2)") (class "Default")
      (node (ref "C22") (pin "2") (pinfunction "2_2") (pintype "passive"))
      (node (ref "R63") (pin "2") (pinfunction "2_2") (pintype "passive"))
    )
    (net (code "37") (name "Net-(D1-Pad+)") (class "Default")
      (node (ref "D1") (pin "+") (pinfunction "+_+") (pintype "bidirectional"))
      (node (ref "R4") (pin "2") (pinfunction "2_2") (pintype "passive"))
      (node (ref "R5") (pin "1") (pinfunction "1_1") (pintype "passive"))
    )
    (net (code "38") (name "Net-(D2-Pad+)") (class "Default")
      (node (ref "D2") (pin "+") (pinfunction "+_+") (pintype "bidirectional"))
      (node (ref "R10") (pin "1") (pinfunction "1_1") (pintype "passive"))
      (node (ref "R9") (pin "2") (pinfunction "2_2") (pintype "passive"))
    )
    (net (code "39") (name "Net-(D3-Pad+)") (class "Default")
      (node (ref "D3") (pin "+") (pinfunction "+_+") (pintype "bidirectional"))
      (node (ref "R14") (pin "2") (pinfunction "2_2") (pintype "passive"))
      (node (ref "R15") (pin "1") (pinfunction "1_1") (pintype "passive"))
    )
    (net (code "40") (name "Net-(D4-Pad+)") (class "Default")
      (node (ref "D4") (pin "+") (pinfunction "+_+") (pintype "bidirectional"))
      (node (ref "R19") (pin "2") (pinfunction "2_2") (pintype "passive"))
      (node (ref "R20") (pin "1") (pinfunction "1_1") (pintype "passive"))
    )
    (net (code "41") (name "Net-(D5-Pad+)") (class "Default")
      (node (ref "D5") (pin "+") (pinfunction "+_+") (pintype "bidirectional"))
      (node (ref "R24") (pin "2") (pinfunction "2_2") (pintype "passive"))
      (node (ref "R25") (pin "1") (pinfunction "1_1") (pintype "passive"))
    )
    (net (code "42") (name "Net-(D6-Pad+)") (class "Default")
      (node (ref "D6") (pin "+") (pinfunction "+_+") (pintype "bidirectional"))
      (node (ref "R29") (pin "2") (pinfunction "2_2") (pintype "passive"))
      (node (ref "R30") (pin "1") (pinfunction "1_1") (pintype "passive"))
    )
    (net (code "43") (name "Net-(D7-Pad+)") (class "Default")
      (node (ref "D7") (pin "+") (pinfunction "+_+") (pintype "bidirectional"))
      (node (ref "R34") (pin "2") (pinfunction "2_2") (pintype "passive"))
      (node (ref "R35") (pin "1") (pinfunction "1_1") (pintype "passive"))
    )
    (net (code "44") (name "Net-(D8-Pad+)") (class "Default")
      (node (ref "D8") (pin "+") (pinfunction "+_+") (pintype "bidirectional"))
      (node (ref "R39") (pin "2") (pinfunction "2_2") (pintype "passive"))
      (node (ref "R40") (pin "1") (pinfunction "1_1") (pintype "passive"))
    )
    (net (code "45") (name "Net-(D9-Pad+)") (class "Default")
      (node (ref "D9") (pin "+") (pinfunction "+_+") (pintype "bidirectional"))
      (node (ref "R44") (pin "2") (pinfunction "2_2") (pintype "passive"))
      (node (ref "R45") (pin "1") (pinfunction "1_1") (pintype "passive"))
    )
    (net (code "46") (name "Net-(LMP1-PadV+)") (class "Default")
      (node (ref "LMP1") (pin "V+") (pinfunction "V+_V+") (pintype "bidirectional"))
      (node (ref "R2") (pin "1") (pinfunction "1_1") (pintype "passive"))
      (node (ref "R3") (pin "2") (pinfunction "2_2") (pintype "passive"))
    )
    (net (code "47") (name "Net-(LMP2-PadV+)") (class "Default")
      (node (ref "LMP2") (pin "V+") (pinfunction "V+_V+") (pintype "bidirectional"))
      (node (ref "R7") (pin "1") (pinfunction "1_1") (pintype "passive"))
      (node (ref "R8") (pin "2") (pinfunction "2_2") (pintype "passive"))
    )
    (net (code "48") (name "Net-(LMP3-PadV+)") (class "Default")
      (node (ref "LMP3") (pin "V+") (pinfunction "V+_V+") (pintype "bidirectional"))
      (node (ref "R12") (pin "1") (pinfunction "1_1") (pintype "passive"))
      (node (ref "R13") (pin "2") (pinfunction "2_2") (pintype "passive"))
    )
    (net (code "49") (name "Net-(LMP4-PadV+)") (class "Default")
      (node (ref "LMP4") (pin "V+") (pinfunction "V+_V+") (pintype "bidirectional"))
      (node (ref "R17") (pin "1") (pinfunction "1_1") (pintype "passive"))
      (node (ref "R18") (pin "2") (pinfunction "2_2") (pintype "passive"))
    )
    (net (code "50") (name "Net-(LMP5-PadV+)") (class "Default")
      (node (ref "LMP5") (pin "V+") (pinfunction "V+_V+") (pintype "bidirectional"))
      (node (ref "R22") (pin "1") (pinfunction "1_1") (pintype "passive"))
      (node (ref "R23") (pin "2") (pinfunction "2_2") (pintype "passive"))
    )
    (net (code "51") (name "Net-(LMP6-PadV+)") (class "Default")
      (node (ref "LMP6") (pin "V+") (pinfunction "V+_V+") (pintype "bidirectional"))
      (node (ref "R27") (pin "1") (pinfunction "1_1") (pintype "passive"))
      (node (ref "R28") (pin "2") (pinfunction "2_2") (pintype "passive"))
    )
    (net (code "52") (name "Net-(LMP7-PadV+)") (class "Default")
      (node (ref "LMP7") (pin "V+") (pinfunction "V+_V+") (pintype "bidirectional"))
      (node (ref "R32") (pin "1") (pinfunction "1_1") (pintype "passive"))
      (node (ref "R33") (pin "2") (pinfunction "2_2") (pintype "passive"))
    )
    (net (code "53") (name "Net-(LMP8-PadV+)") (class "Default")
      (node (ref "LMP8") (pin "V+") (pinfunction "V+_V+") (pintype "bidirectional"))
      (node (ref "R37") (pin "1") (pinfunction "1_1") (pintype "passive"))
      (node (ref "R38") (pin "2") (pinfunction "2_2") (pintype "passive"))
    )
    (net (code "54") (name "Net-(LMP9-PadV+)") (class "Default")
      (node (ref "LMP9") (pin "V+") (pinfunction "V+_V+") (pintype "bidirectional"))
      (node (ref "R42") (pin "1") (pinfunction "1_1") (pintype "passive"))
      (node (ref "R43") (pin "2") (pinfunction "2_2") (pintype "passive"))
    )
    (net (code "55") (name "Net-(R1-1)") (class "Default")
      (node (ref "MOS1") (pin "DRAIN") (pinfunction "DRAIN_DRAIN") (pintype "bidirectional"))
      (node (ref "R1") (pin "P$1") (pinfunction "1_P$1") (pintype "passive"))
    )
    (net (code "56") (name "Net-(R6-1)") (class "Default")
      (node (ref "MOS2") (pin "DRAIN") (pinfunction "DRAIN_DRAIN") (pintype "bidirectional"))
      (node (ref "R6") (pin "P$1") (pinfunction "1_P$1") (pintype "passive"))
    )
    (net (code "57") (name "Net-(R6-2)") (class "Default")
      (node (ref "C1") (pin "-") (pinfunction "-_-") (pintype "bidirectional"))
      (node (ref "C3") (pin "+") (pinfunction "+_+") (pintype "bidirectional"))
      (node (ref "D1") (pin "-") (pinfunction "-_-") (pintype "bidirectional"))
      (node (ref "D1") (pin "NOT_USE") (pinfunction "NOT_USE_NOT_USE") (pintype "bidirectional"))
      (node (ref "LMP1") (pin "IN-") (pinfunction "IN-_IN-") (pintype "bidirectional"))
      (node (ref "LMP2") (pin "IN+") (pinfunction "IN+_IN+") (pintype "bidirectional"))
      (node (ref "MOS1") (pin "SOURCE") (pinfunction "SOURCE_SOURCE") (pintype "bidirectional"))
      (node (ref "R3") (pin "1") (pinfunction "1_1") (pintype "passive"))
      (node (ref "R6") (pin "P$2") (pinfunction "2_P$2") (pintype "passive"))
      (node (ref "R7") (pin "2") (pinfunction "2_2") (pintype "passive"))
      (node (ref "R9") (pin "1") (pinfunction "1_1") (pintype "passive"))
    )
    (net (code "58") (name "Net-(R11-1)") (class "Default")
      (node (ref "MOS3") (pin "DRAIN") (pinfunction "DRAIN_DRAIN") (pintype "bidirectional"))
      (node (ref "R11") (pin "P$1") (pinfunction "1_P$1") (pintype "passive"))
    )
    (net (code "59") (name "Net-(R11-2)") (class "Default")
      (node (ref "C3") (pin "-") (pinfunction "-_-") (pintype "bidirectional"))
      (node (ref "C5") (pin "+") (pinfunction "+_+") (pintype "bidirectional"))
      (node (ref "D2") (pin "-") (pinfunction "-_-") (pintype "bidirectional"))
      (node (ref "D2") (pin "NOT_USE") (pinfunction "NOT_USE_NOT_USE") (pintype "bidirectional"))
      (node (ref "LMP2") (pin "IN-") (pinfunction "IN-_IN-") (pintype "bidirectional"))
      (node (ref "LMP3") (pin "IN+") (pinfunction "IN+_IN+") (pintype "bidirectional"))
      (node (ref "MOS2") (pin "SOURCE") (pinfunction "SOURCE_SOURCE") (pintype "bidirectional"))
      (node (ref "R11") (pin "P$2") (pinfunction "2_P$2") (pintype "passive"))
      (node (ref "R12") (pin "2") (pinfunction "2_2") (pintype "passive"))
      (node (ref "R14") (pin "1") (pinfunction "1_1") (pintype "passive"))
      (node (ref "R8") (pin "1") (pinfunction "1_1") (pintype "passive"))
    )
    (net (code "60") (name "Net-(R16-1)") (class "Default")
      (node (ref "MOS4") (pin "DRAIN") (pinfunction "DRAIN_DRAIN") (pintype "bidirectional"))
      (node (ref "R16") (pin "P$1") (pinfunction "1_P$1") (pintype "passive"))
    )
    (net (code "61") (name "Net-(R16-2)") (class "Default")
      (node (ref "C5") (pin "-") (pinfunction "-_-") (pintype "bidirectional"))
      (node (ref "C7") (pin "+") (pinfunction "+_+") (pintype "bidirectional"))
      (node (ref "D3") (pin "-") (pinfunction "-_-") (pintype "bidirectional"))
      (node (ref "D3") (pin "NOT_USE") (pinfunction "NOT_USE_NOT_USE") (pintype "bidirectional"))
      (node (ref "LMP3") (pin "IN-") (pinfunction "IN-_IN-") (pintype "bidirectional"))
      (node (ref "LMP4") (pin "IN+") (pinfunction "IN+_IN+") (pintype "bidirectional"))
      (node (ref "MOS3") (pin "SOURCE") (pinfunction "SOURCE_SOURCE") (pintype "bidirectional"))
      (node (ref "R13") (pin "1") (pinfunction "1_1") (pintype "passive"))
      (node (ref "R16") (pin "P$2") (pinfunction "2_P$2") (pintype "passive"))
      (node (ref "R17") (pin "2") (pinfunction "2_2") (pintype "passive"))
      (node (ref "R19") (pin "1") (pinfunction "1_1") (pintype "passive"))
    )
    (net (code "62") (name "Net-(R21-1)") (class "Default")
      (node (ref "MOS5") (pin "DRAIN") (pinfunction "DRAIN_DRAIN") (pintype "bidirectional"))
      (node (ref "R21") (pin "P$1") (pinfunction "1_P$1") (pintype "passive"))
    )
    (net (code "63") (name "Net-(R21-2)") (class "Default")
      (node (ref "C7") (pin "-") (pinfunction "-_-") (pintype "bidirectional"))
      (node (ref "C9") (pin "+") (pinfunction "+_+") (pintype "bidirectional"))
      (node (ref "D4") (pin "-") (pinfunction "-_-") (pintype "bidirectional"))
      (node (ref "D4") (pin "NOT_USE") (pinfunction "NOT_USE_NOT_USE") (pintype "bidirectional"))
      (node (ref "LMP4") (pin "IN-") (pinfunction "IN-_IN-") (pintype "bidirectional"))
      (node (ref "LMP5") (pin "IN+") (pinfunction "IN+_IN+") (pintype "bidirectional"))
      (node (ref "MOS4") (pin "SOURCE") (pinfunction "SOURCE_SOURCE") (pintype "bidirectional"))
      (node (ref "R18") (pin "1") (pinfunction "1_1") (pintype "passive"))
      (node (ref "R21") (pin "P$2") (pinfunction "2_P$2") (pintype "passive"))
      (node (ref "R22") (pin "2") (pinfunction "2_2") (pintype "passive"))
      (node (ref "R24") (pin "1") (pinfunction "1_1") (pintype "passive"))
    )
    (net (code "64") (name "Net-(R26-1)") (class "Default")
      (node (ref "MOS6") (pin "DRAIN") (pinfunction "DRAIN_DRAIN") (pintype "bidirectional"))
      (node (ref "R26") (pin "P$1") (pinfunction "1_P$1") (pintype "passive"))
    )
    (net (code "65") (name "Net-(R26-2)") (class "Default")
      (node (ref "C11") (pin "+") (pinfunction "+_+") (pintype "bidirectional"))
      (node (ref "C9") (pin "-") (pinfunction "-_-") (pintype "bidirectional"))
      (node (ref "D5") (pin "-") (pinfunction "-_-") (pintype "bidirectional"))
      (node (ref "D5") (pin "NOT_USE") (pinfunction "NOT_USE_NOT_USE") (pintype "bidirectional"))
      (node (ref "LMP5") (pin "IN-") (pinfunction "IN-_IN-") (pintype "bidirectional"))
      (node (ref "LMP6") (pin "IN+") (pinfunction "IN+_IN+") (pintype "bidirectional"))
      (node (ref "MOS5") (pin "SOURCE") (pinfunction "SOURCE_SOURCE") (pintype "bidirectional"))
      (node (ref "R23") (pin "1") (pinfunction "1_1") (pintype "passive"))
      (node (ref "R26") (pin "P$2") (pinfunction "2_P$2") (pintype "passive"))
      (node (ref "R27") (pin "2") (pinfunction "2_2") (pintype "passive"))
      (node (ref "R29") (pin "1") (pinfunction "1_1") (pintype "passive"))
    )
    (net (code "66") (name "Net-(R31-1)") (class "Default")
      (node (ref "MOS7") (pin "DRAIN") (pinfunction "DRAIN_DRAIN") (pintype "bidirectional"))
      (node (ref "R31") (pin "P$1") (pinfunction "1_P$1") (pintype "passive"))
    )
    (net (code "67") (name "Net-(R31-2)") (class "Default")
      (node (ref "C11") (pin "-") (pinfunction "-_-") (pintype "bidirectional"))
      (node (ref "C13") (pin "+") (pinfunction "+_+") (pintype "bidirectional"))
      (node (ref "D6") (pin "-") (pinfunction "-_-") (pintype "bidirectional"))
      (node (ref "D6") (pin "NOT_USE") (pinfunction "NOT_USE_NOT_USE") (pintype "bidirectional"))
      (node (ref "LMP6") (pin "IN-") (pinfunction "IN-_IN-") (pintype "bidirectional"))
      (node (ref "LMP7") (pin "IN+") (pinfunction "IN+_IN+") (pintype "bidirectional"))
      (node (ref "MOS6") (pin "SOURCE") (pinfunction "SOURCE_SOURCE") (pintype "bidirectional"))
      (node (ref "R28") (pin "1") (pinfunction "1_1") (pintype "passive"))
      (node (ref "R31") (pin "P$2") (pinfunction "2_P$2") (pintype "passive"))
      (node (ref "R32") (pin "2") (pinfunction "2_2") (pintype "passive"))
      (node (ref "R34") (pin "1") (pinfunction "1_1") (pintype "passive"))
    )
    (net (code "68") (name "Net-(R36-1)") (class "Default")
      (node (ref "MOS8") (pin "DRAIN") (pinfunction "DRAIN_DRAIN") (pintype "bidirectional"))
      (node (ref "R36") (pin "P$1") (pinfunction "1_P$1") (pintype "passive"))
    )
    (net (code "69") (name "Net-(R36-2)") (class "Default")
      (node (ref "C13") (pin "-") (pinfunction "-_-") (pintype "bidirectional"))
      (node (ref "C15") (pin "+") (pinfunction "+_+") (pintype "bidirectional"))
      (node (ref "D7") (pin "-") (pinfunction "-_-") (pintype "bidirectional"))
      (node (ref "D7") (pin "NOT_USE") (pinfunction "NOT_USE_NOT_USE") (pintype "bidirectional"))
      (node (ref "LMP7") (pin "IN-") (pinfunction "IN-_IN-") (pintype "bidirectional"))
      (node (ref "LMP8") (pin "IN+") (pinfunction "IN+_IN+") (pintype "bidirectional"))
      (node (ref "MOS7") (pin "SOURCE") (pinfunction "SOURCE_SOURCE") (pintype "bidirectional"))
      (node (ref "R33") (pin "1") (pinfunction "1_1") (pintype "passive"))
      (node (ref "R36") (pin "P$2") (pinfunction "2_P$2") (pintype "passive"))
      (node (ref "R37") (pin "2") (pinfunction "2_2") (pintype "passive"))
      (node (ref "R39") (pin "1") (pinfunction "1_1") (pintype "passive"))
    )
    (net (code "70") (name "Net-(R41-1)") (class "Default")
      (node (ref "MOS9") (pin "DRAIN") (pinfunction "DRAIN_DRAIN") (pintype "bidirectional"))
      (node (ref "R41") (pin "P$1") (pinfunction "1_P$1") (pintype "passive"))
    )
    (net (code "71") (name "Net-(R41-2)") (class "Default")
      (node (ref "C15") (pin "-") (pinfunction "-_-") (pintype "bidirectional"))
      (node (ref "C17") (pin "+") (pinfunction "+_+") (pintype "bidirectional"))
      (node (ref "D8") (pin "-") (pinfunction "-_-") (pintype "bidirectional"))
      (node (ref "D8") (pin "NOT_USE") (pinfunction "NOT_USE_NOT_USE") (pintype "bidirectional"))
      (node (ref "LMP8") (pin "IN-") (pinfunction "IN-_IN-") (pintype "bidirectional"))
      (node (ref "LMP9") (pin "IN+") (pinfunction "IN+_IN+") (pintype "bidirectional"))
      (node (ref "MOS8") (pin "SOURCE") (pinfunction "SOURCE_SOURCE") (pintype "bidirectional"))
      (node (ref "R38") (pin "1") (pinfunction "1_1") (pintype "passive"))
      (node (ref "R41") (pin "P$2") (pinfunction "2_P$2") (pintype "passive"))
      (node (ref "R42") (pin "2") (pinfunction "2_2") (pintype "passive"))
      (node (ref "R44") (pin "1") (pinfunction "1_1") (pintype "passive"))
    )
    (net (code "72") (name "Net-(R53-Pad2)") (class "Default")
      (node (ref "R53") (pin "2") (pinfunction "2_2") (pintype "passive"))
      (node (ref "R55") (pin "1") (pinfunction "1_1") (pintype "passive"))
      (node (ref "U$10") (pin "13") (pinfunction "13_13") (pintype "bidirectional"))
    )
    (net (code "73") (name "Net-(R54-Pad1)") (class "Default")
      (node (ref "R54") (pin "1") (pinfunction "1_1") (pintype "passive"))
      (node (ref "U$3") (pin "B") (pinfunction "B_B") (pintype "bidirectional"))
    )
    (net (code "74") (name "Net-(R54-Pad2)") (class "Default")
      (node (ref "R54") (pin "2") (pinfunction "2_2") (pintype "passive"))
      (node (ref "U$10") (pin "12") (pinfunction "12_12") (pintype "bidirectional"))
    )
    (net (code "75") (name "Net-(R55-Pad2)") (class "Default")
      (node (ref "R55") (pin "2") (pinfunction "2_2") (pintype "passive"))
      (node (ref "U$5") (pin "B") (pinfunction "B_B") (pintype "bidirectional"))
    )
    (net (code "76") (name "Net-(R56-Pad1)") (class "Default")
      (node (ref "R56") (pin "1") (pinfunction "1_1") (pintype "passive"))
      (node (ref "U$6") (pin "B") (pinfunction "B_B") (pintype "bidirectional"))
    )
    (net (code "77") (name "Net-(R56-Pad2)") (class "Default")
      (node (ref "R56") (pin "2") (pinfunction "2_2") (pintype "passive"))
      (node (ref "U$10") (pin "11") (pinfunction "11_11") (pintype "bidirectional"))
    )
    (net (code "78") (name "Net-(U$7-A-7)") (class "Default")
      (node (ref "R46") (pin "2") (pinfunction "2_2") (pintype "passive"))
      (node (ref "U$7") (pin "7") (pinfunction "A-7_7") (pintype "bidirectional"))
      (node (ref "U$8") (pin "7") (pinfunction "A-7_7") (pintype "bidirectional"))
      (node (ref "U$9") (pin "7") (pinfunction "A-7_7") (pintype "bidirectional"))
    )
    (net (code "79") (name "Net-(U$7-B-6)") (class "Default")
      (node (ref "R47") (pin "2") (pinfunction "2_2") (pintype "passive"))
      (node (ref "U$7") (pin "6") (pinfunction "B-6_6") (pintype "bidirectional"))
      (node (ref "U$8") (pin "6") (pinfunction "B-6_6") (pintype "bidirectional"))
      (node (ref "U$9") (pin "6") (pinfunction "B-6_6") (pintype "bidirectional"))
    )
    (net (code "80") (name "Net-(U$7-C-4)") (class "Default")
      (node (ref "R48") (pin "2") (pinfunction "2_2") (pintype "passive"))
      (node (ref "U$7") (pin "4") (pinfunction "C-4_4") (pintype "bidirectional"))
      (node (ref "U$8") (pin "4") (pinfunction "C-4_4") (pintype "bidirectional"))
      (node (ref "U$9") (pin "4") (pinfunction "C-4_4") (pintype "bidirectional"))
    )
    (net (code "81") (name "Net-(U$7-D-2)") (class "Default")
      (node (ref "R49") (pin "2") (pinfunction "2_2") (pintype "passive"))
      (node (ref "U$7") (pin "2") (pinfunction "D-2_2") (pintype "bidirectional"))
      (node (ref "U$8") (pin "2") (pinfunction "D-2_2") (pintype "bidirectional"))
      (node (ref "U$9") (pin "2") (pinfunction "D-2_2") (pintype "bidirectional"))
    )
    (net (code "82") (name "Net-(U$7-E-1)") (class "Default")
      (node (ref "R50") (pin "2") (pinfunction "2_2") (pintype "passive"))
      (node (ref "U$7") (pin "1") (pinfunction "E-1_1") (pintype "bidirectional"))
      (node (ref "U$8") (pin "1") (pinfunction "E-1_1") (pintype "bidirectional"))
      (node (ref "U$9") (pin "1") (pinfunction "E-1_1") (pintype "bidirectional"))
    )
    (net (code "83") (name "Net-(U$7-F-9)") (class "Default")
      (node (ref "R51") (pin "2") (pinfunction "2_2") (pintype "passive"))
      (node (ref "U$7") (pin "9") (pinfunction "F-9_9") (pintype "bidirectional"))
      (node (ref "U$8") (pin "9") (pinfunction "F-9_9") (pintype "bidirectional"))
      (node (ref "U$9") (pin "9") (pinfunction "F-9_9") (pintype "bidirectional"))
    )
    (net (code "84") (name "Net-(U$7-G-10)") (class "Default")
      (node (ref "R52") (pin "2") (pinfunction "2_2") (pintype "passive"))
      (node (ref "U$7") (pin "10") (pinfunction "G-10_10") (pintype "bidirectional"))
      (node (ref "U$8") (pin "10") (pinfunction "G-10_10") (pintype "bidirectional"))
      (node (ref "U$9") (pin "10") (pinfunction "G-10_10") (pintype "bidirectional"))
    )
    (net (code "85") (name "Net-(U$7-G1-3)") (class "Default")
      (node (ref "U$3") (pin "C") (pinfunction "C_C") (pintype "bidirectional"))
      (node (ref "U$3") (pin "C2") (pinfunction "C_C2") (pintype "bidirectional"))
      (node (ref "U$7") (pin "3") (pinfunction "G1-3_3") (pintype "bidirectional"))
      (node (ref "U$7") (pin "8") (pinfunction "G2-8_8") (pintype "bidirectional"))
    )
    (net (code "86") (name "Net-(U$8-G1-3)") (class "Default")
      (node (ref "U$6") (pin "C") (pinfunction "C_C") (pintype "bidirectional"))
      (node (ref "U$6") (pin "C2") (pinfunction "C_C2") (pintype "bidirectional"))
      (node (ref "U$8") (pin "3") (pinfunction "G1-3_3") (pintype "bidirectional"))
      (node (ref "U$8") (pin "8") (pinfunction "G2-8_8") (pintype "bidirectional"))
    )
    (net (code "87") (name "Net-(U$9-DP-5)") (class "Default")
      (node (ref "R53") (pin "1") (pinfunction "1_1") (pintype "passive"))
      (node (ref "U$9") (pin "5") (pinfunction "DP-5_5") (pintype "bidirectional"))
    )
    (net (code "88") (name "Net-(U$9-G1-3)") (class "Default")
      (node (ref "U$5") (pin "C") (pinfunction "C_C") (pintype "bidirectional"))
      (node (ref "U$5") (pin "C2") (pinfunction "C_C2") (pintype "bidirectional"))
      (node (ref "U$9") (pin "3") (pinfunction "G1-3_3") (pintype "bidirectional"))
      (node (ref "U$9") (pin "8") (pinfunction "G2-8_8") (pintype "bidirectional"))
    )
    (net (code "89") (name "Net-(VR1-CW)") (class "Default")
      (node (ref "C19") (pin "1") (pinfunction "1_1") (pintype "passive"))
      (node (ref "D10") (pin "C") (pinfunction "C_C") (pintype "passive"))
      (node (ref "R57") (pin "2") (pinfunction "2_2") (pintype "passive"))
      (node (ref "U$10") (pin "3") (pinfunction "3_3") (pintype "bidirectional"))
      (node (ref "VR1") (pin "1") (pinfunction "CW_1") (pintype "passive"))
    )
    (net (code "90") (name "VIN") (class "Default")
      (node (ref "C1") (pin "+") (pinfunction "+_+") (pintype "bidirectional"))
      (node (ref "LMP1") (pin "IN+") (pinfunction "IN+_IN+") (pintype "bidirectional"))
      (node (ref "PWR_IN") (pin "+") (pinfunction "VCC_+") (pintype "bidirectional"))
      (node (ref "PWR_OUT") (pin "+") (pinfunction "VCC_+") (pintype "bidirectional"))
      (node (ref "R1") (pin "P$2") (pinfunction "2_P$2") (pintype "passive"))
      (node (ref "R2") (pin "2") (pinfunction "2_2") (pintype "passive"))
      (node (ref "R4") (pin "1") (pinfunction "1_1") (pintype "passive"))
      (node (ref "R57") (pin "1") (pinfunction "1_1") (pintype "passive"))
    )
    (net (code "91") (name "unconnected-(U$7-DP-5-Pad5)") (class "Default")
      (node (ref "U$7") (pin "5") (pinfunction "DP-5_5") (pintype "bidirectional"))
    )
    (net (code "92") (name "unconnected-(U$8-DP-5-Pad5)") (class "Default")
      (node (ref "U$8") (pin "5") (pinfunction "DP-5_5") (pintype "bidirectional"))
    )
    (net (code "93") (name "unconnected-(U$10-Pad4)") (class "Default")
      (node (ref "U$10") (pin "4") (pinfunction "4_4") (pintype "bidirectional"))
    )
  )
)
